# Sheet1.net
KiCad netlist of a schematic drawn in Altium Designer
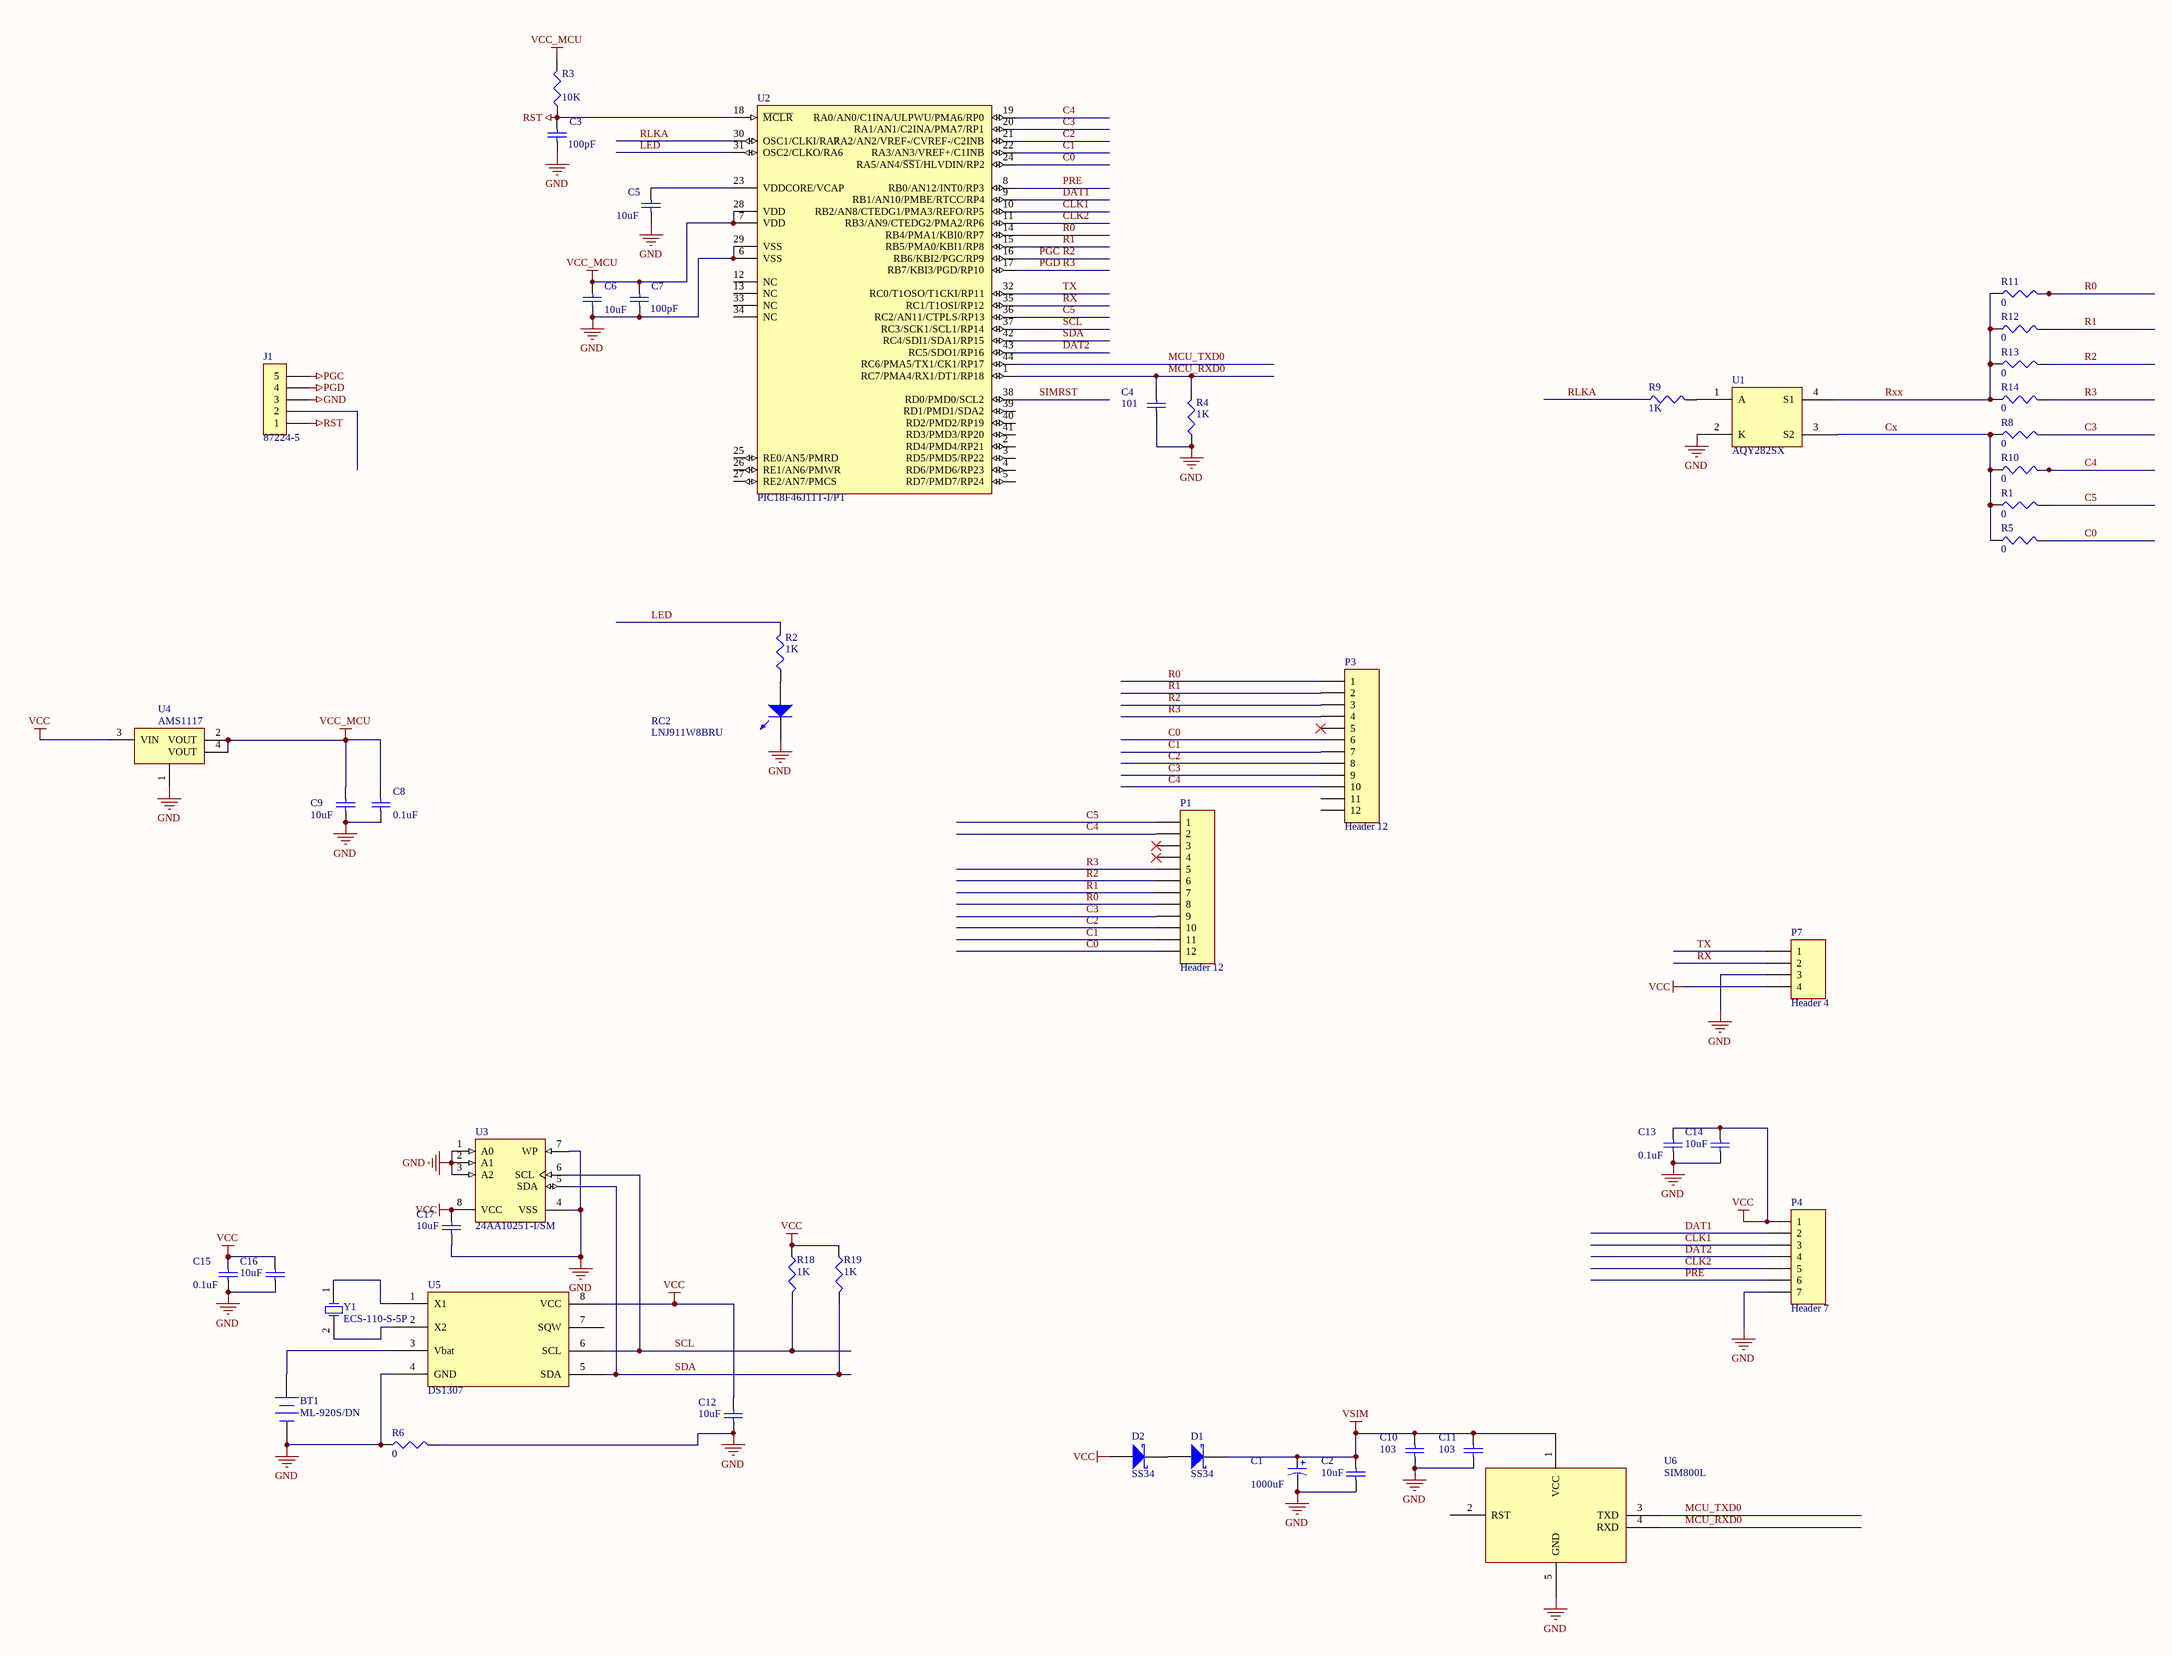
[diagram p0: Sheet1.SchDoc]

(export (version "E")
  (design (tool "Eeschema 10.0.6"))
  (components
    (comp (ref "BT1")
      (value "ML-920S/DN")
      (footprint "ML-920S/DN")
      (description "Multicell Battery")
      (fields (field (name "PUBLISHER") "Altium Limited"))
      (libsource (lib "Miscellaneous Devices") (part "Battery"))
    )
    (comp (ref "C1")
      (value "1000uF")
      (footprint "CAP8x8")
      (description "CAP ALUM 1000UF 10V 20% SMD")
      (fields (field (name "Comment") "EEE-FT1A102AP") (field (name "PUBLISHER") "Altium Limited"))
      (libsource (lib "Miscellaneous Devices") (part "Cap Pol1"))
    )
    (comp (ref "C2")
      (value "10uF")
      (footprint "RESC2012L")
      (description "CAP CER 10UF 10V Y5V 0805")
      (fields (field (name "Comment") "LMK212F106ZG-T") (field (name "PUBLISHER") "Altium Limited"))
      (libsource (lib "Miscellaneous Devices") (part "Cap"))
    )
    (comp (ref "C3")
      (value "100pF")
      (footprint "CAPC2013X05N")
      (description "Capacitor (Semiconductor SIM Model)")
      (fields (field (name "Comment") "Cap Semi") (field (name "PUBLISHER") "Altium Limited"))
      (libsource (lib "Miscellaneous Devices") (part "Cap Semi"))
    )
    (comp (ref "C4")
      (value "101")
      (footprint "RESC2012L")
      (description "CAP CER 10UF 10V Y5V 0805")
      (fields (field (name "Comment") "LMK212F106ZG-T") (field (name "PUBLISHER") "Altium Limited"))
      (libsource (lib "Miscellaneous Devices") (part "Cap"))
    )
    (comp (ref "C5")
      (value "10uF")
      (footprint "CAPC2013X05N")
      (description "Capacitor (Semiconductor SIM Model)")
      (fields (field (name "Comment") "Cap Semi") (field (name "PUBLISHER") "Altium Limited"))
      (libsource (lib "Miscellaneous Devices") (part "Cap Semi"))
    )
    (comp (ref "C6")
      (value "10uF")
      (footprint "CAPC2013X05N")
      (description "Capacitor (Semiconductor SIM Model)")
      (fields (field (name "Comment") "Cap Semi") (field (name "PUBLISHER") "Altium Limited"))
      (libsource (lib "Miscellaneous Devices") (part "Cap Semi"))
    )
    (comp (ref "C7")
      (value "100pF")
      (footprint "CAPC2013X05N")
      (description "Capacitor (Semiconductor SIM Model)")
      (fields (field (name "Comment") "Cap Semi") (field (name "PUBLISHER") "Altium Limited"))
      (libsource (lib "Miscellaneous Devices") (part "Cap Semi"))
    )
    (comp (ref "C8")
      (value "0.1uF")
      (footprint "RESC2012L")
      (description "CAP CER 0.1UF 50V Y5V 0805")
      (fields (field (name "Comment") "CL21F104ZBCNNNC") (field (name "PUBLISHER") "Altium Limited"))
      (libsource (lib "Miscellaneous Devices") (part "Cap"))
    )
    (comp (ref "C9")
      (value "10uF")
      (footprint "RESC2012L")
      (description "CAP CER 10UF 10V Y5V 0805")
      (fields (field (name "Comment") "LMK212F106ZG-T") (field (name "PUBLISHER") "Altium Limited"))
      (libsource (lib "Miscellaneous Devices") (part "Cap"))
    )
    (comp (ref "C10")
      (value "103")
      (footprint "RESC2012L")
      (description "CAP CER 10UF 10V Y5V 0805")
      (fields (field (name "Comment") "LMK212F106ZG-T") (field (name "PUBLISHER") "Altium Limited"))
      (libsource (lib "Miscellaneous Devices") (part "Cap"))
    )
    (comp (ref "C11")
      (value "103")
      (footprint "RESC2012L")
      (description "CAP CER 10UF 10V Y5V 0805")
      (fields (field (name "Comment") "LMK212F106ZG-T") (field (name "PUBLISHER") "Altium Limited"))
      (libsource (lib "Miscellaneous Devices") (part "Cap"))
    )
    (comp (ref "C12")
      (value "10uF")
      (footprint "RESC2012L")
      (description "CAP CER 10UF 10V Y5V 0805")
      (fields (field (name "Comment") "LMK212F106ZG-T") (field (name "PUBLISHER") "Altium Limited"))
      (libsource (lib "Miscellaneous Devices") (part "Cap"))
    )
    (comp (ref "C13")
      (value "0.1uF")
      (footprint "RESC2012L")
      (description "CAP CER 0.1UF 50V Y5V 0805")
      (fields (field (name "Comment") "CL21F104ZBCNNNC") (field (name "PUBLISHER") "Altium Limited"))
      (libsource (lib "Miscellaneous Devices") (part "Cap"))
    )
    (comp (ref "C14")
      (value "10uF")
      (footprint "RESC2012L")
      (description "CAP CER 10UF 10V Y5V 0805")
      (fields (field (name "Comment") "LMK212F106ZG-T") (field (name "PUBLISHER") "Altium Limited"))
      (libsource (lib "Miscellaneous Devices") (part "Cap"))
    )
    (comp (ref "C15")
      (value "0.1uF")
      (footprint "RESC2012L")
      (description "CAP CER 0.1UF 50V Y5V 0805")
      (fields (field (name "Comment") "CL21F104ZBCNNNC") (field (name "PUBLISHER") "Altium Limited"))
      (libsource (lib "Miscellaneous Devices") (part "Cap"))
    )
    (comp (ref "C16")
      (value "10uF")
      (footprint "RESC2012L")
      (description "CAP CER 10UF 10V Y5V 0805")
      (fields (field (name "Comment") "LMK212F106ZG-T") (field (name "PUBLISHER") "Altium Limited"))
      (libsource (lib "Miscellaneous Devices") (part "Cap"))
    )
    (comp (ref "C17")
      (value "10uF")
      (footprint "RESC2012L")
      (description "CAP CER 10UF 10V Y5V 0805")
      (fields (field (name "Comment") "LMK212F106ZG-T") (field (name "PUBLISHER") "Altium Limited"))
      (libsource (lib "Miscellaneous Devices") (part "Cap"))
    )
    (comp (ref "D1")
      (value "SS34")
      (footprint "SMB")
      (description "DIODE SCHOTTKY 40V 3A SMC")
      (fields (field (name "PUBLISHER") "Altium Limited"))
      (libsource (lib "Schlib1") (part "D Schottky SS34"))
    )
    (comp (ref "D2")
      (value "SS34")
      (footprint "SMB")
      (description "DIODE SCHOTTKY 40V 3A SMC")
      (fields (field (name "PUBLISHER") "Altium Limited"))
      (libsource (lib "Schlib1") (part "D Schottky SS34"))
    )
    (comp (ref "J1")
      (value "87224-5")
      (footprint "CON5")
      (description "CONN HEADER VERT .100 5POS 15AU")
      (libsource (lib "*") (part "CON5"))
    )
    (comp (ref "P1")
      (value "Header 12")
      (footprint "HDR1X12")
      (description "Header, 12-Pin")
      (fields (field (name "PUBLISHER") "Altium Limited"))
      (libsource (lib "Miscellaneous Connectors") (part "Header 12"))
    )
    (comp (ref "P3")
      (value "Header 12")
      (footprint "HDR1X12")
      (description "Header, 12-Pin")
      (fields (field (name "PUBLISHER") "Altium Limited"))
      (libsource (lib "Miscellaneous Connectors") (part "Header 12"))
    )
    (comp (ref "P4")
      (value "Header 7")
      (footprint "HDR1X7")
      (description "Header, 7-Pin")
      (fields (field (name "PUBLISHER") "Altium Limited"))
      (libsource (lib "Miscellaneous Connectors") (part "Header 7"))
    )
    (comp (ref "P7")
      (value "Header 4")
      (footprint "HDR1X4")
      (description "Header, 4-Pin")
      (fields (field (name "PUBLISHER") "Altium Limited"))
      (libsource (lib "Miscellaneous Connectors") (part "Header 4"))
    )
    (comp (ref "R1")
      (value "0")
      (footprint "JUM1")
      (description "RES 330 OHM 1/8W 5% 0805 SMD")
      (fields (field (name "Comment") "ERJ-6GEYJ331V") (field (name "PUBLISHER") "Altium Limited"))
      (libsource (lib "Miscellaneous Devices") (part "Res3"))
    )
    (comp (ref "R2")
      (value "1K")
      (footprint "RESC2012L")
      (description "RES 1K OHM 1/8W 5% 0805 SMD")
      (fields (field (name "Comment") "ERJ-6GEYJ102V") (field (name "PUBLISHER") "Altium Limited"))
      (libsource (lib "Miscellaneous Devices") (part "Res3"))
    )
    (comp (ref "R3")
      (value "10K")
      (footprint "RESC2013X05N")
      (description "Resistor")
      (fields (field (name "Comment") "Res3") (field (name "PUBLISHER") "Altium Limited"))
      (libsource (lib "Miscellaneous Devices") (part "Res3"))
    )
    (comp (ref "R4")
      (value "1K")
      (footprint "RESC2012L")
      (description "RES 1K OHM 1/8W 5% 0805 SMD")
      (fields (field (name "Comment") "ERJ-6GEYJ102V") (field (name "PUBLISHER") "Altium Limited"))
      (libsource (lib "Miscellaneous Devices") (part "Res3"))
    )
    (comp (ref "R5")
      (value "0")
      (footprint "JUM1")
      (description "RES 330 OHM 1/8W 5% 0805 SMD")
      (fields (field (name "Comment") "ERJ-6GEYJ331V") (field (name "PUBLISHER") "Altium Limited"))
      (libsource (lib "Miscellaneous Devices") (part "Res3"))
    )
    (comp (ref "R6")
      (value "0")
      (footprint "JUM1")
      (description "RES 330 OHM 1/8W 5% 0805 SMD")
      (fields (field (name "Comment") "ERJ-6GEYJ331V") (field (name "PUBLISHER") "Altium Limited"))
      (libsource (lib "Miscellaneous Devices") (part "Res3"))
    )
    (comp (ref "R8")
      (value "0")
      (footprint "JUM1")
      (description "RES 330 OHM 1/8W 5% 0805 SMD")
      (fields (field (name "Comment") "ERJ-6GEYJ331V") (field (name "PUBLISHER") "Altium Limited"))
      (libsource (lib "Miscellaneous Devices") (part "Res3"))
    )
    (comp (ref "R9")
      (value "1K")
      (footprint "RESC2012L")
      (description "RES 330 OHM 1/8W 5% 0805 SMD")
      (fields (field (name "Comment") "ERJ-6GEYJ331V") (field (name "PUBLISHER") "Altium Limited"))
      (libsource (lib "Miscellaneous Devices") (part "Res3"))
    )
    (comp (ref "R10")
      (value "0")
      (footprint "JUM1")
      (description "RES 330 OHM 1/8W 5% 0805 SMD")
      (fields (field (name "Comment") "ERJ-6GEYJ331V") (field (name "PUBLISHER") "Altium Limited"))
      (libsource (lib "Miscellaneous Devices") (part "Res3"))
    )
    (comp (ref "R11")
      (value "0")
      (footprint "JUM1")
      (description "RES 330 OHM 1/8W 5% 0805 SMD")
      (fields (field (name "Comment") "ERJ-6GEYJ331V") (field (name "PUBLISHER") "Altium Limited"))
      (libsource (lib "Miscellaneous Devices") (part "Res3"))
    )
    (comp (ref "R12")
      (value "0")
      (footprint "JUM1")
      (description "RES 330 OHM 1/8W 5% 0805 SMD")
      (fields (field (name "Comment") "ERJ-6GEYJ331V") (field (name "PUBLISHER") "Altium Limited"))
      (libsource (lib "Miscellaneous Devices") (part "Res3"))
    )
    (comp (ref "R13")
      (value "0")
      (footprint "JUM1")
      (description "RES 330 OHM 1/8W 5% 0805 SMD")
      (fields (field (name "Comment") "ERJ-6GEYJ331V") (field (name "PUBLISHER") "Altium Limited"))
      (libsource (lib "Miscellaneous Devices") (part "Res3"))
    )
    (comp (ref "R14")
      (value "0")
      (footprint "JUM1")
      (description "RES 330 OHM 1/8W 5% 0805 SMD")
      (fields (field (name "Comment") "ERJ-6GEYJ331V") (field (name "PUBLISHER") "Altium Limited"))
      (libsource (lib "Miscellaneous Devices") (part "Res3"))
    )
    (comp (ref "R18")
      (value "1K")
      (footprint "RESC2012L")
      (description "RES 330 OHM 1/8W 5% 0805 SMD")
      (fields (field (name "Comment") "ERJ-6GEYJ331V") (field (name "PUBLISHER") "Altium Limited"))
      (libsource (lib "Miscellaneous Devices") (part "Res3"))
    )
    (comp (ref "R19")
      (value "1K")
      (footprint "RESC2012L")
      (description "RES 330 OHM 1/8W 5% 0805 SMD")
      (fields (field (name "Comment") "ERJ-6GEYJ331V") (field (name "PUBLISHER") "Altium Limited"))
      (libsource (lib "Miscellaneous Devices") (part "Res3"))
    )
    (comp (ref "RC2")
      (value "LNJ911W8BRU")
      (footprint "CD3216-1206")
      (description "LED BLUE THRU BOARD 1206")
      (libsource (lib "AM335X_ZCZ") (part "LEDRED1206"))
    )
    (comp (ref "U1")
      (value "AQY282SX")
      (footprint "SOP4")
      (description "RELAY OPTO 60VAC/DC 500MA 4-SOP")
      (fields (field (name "DIGI-KEY PART NUMBER") "255-3393-2-ND"))
      (libsource (lib "Schlib1") (part "AQY282SX"))
    )
    (comp (ref "U2")
      (value "PIC18F46J11T-I/PT")
      (footprint "TQFP-PT44_N")
      (fields (field (name "PUBLISHER") "Altium Limited"))
      (libsource (lib "Microchip Microcontroller 8-Bit PIC18") (part "PIC18F46J11T-I/PT"))
    )
    (comp (ref "U3")
      (value "24AA1025T-I/SM")
      (footprint "SOIJ-SM8_N")
      (description "1 Mbit, 400kHz, 1.7V, I2C Serial EEPROM, 8-Pin SOIC 208mil, Industrial Temperature, Tape and Reel")
      (fields (field (name "PUBLISHER") "Altium Limited"))
      (libsource (lib "Microchip Memory I2C Serial EEPROM") (part "24AA1025T-I/SM"))
    )
    (comp (ref "U4")
      (value "AMS1117")
      (footprint "SOT223-4M")
      (description "Adjustable Precision Shunt Regulator")
      (fields (field (name "PUBLISHER") "Altium Limited"))
      (libsource (lib "Schlib1") (part "AMS1117"))
    )
    (comp (ref "U5") (value "DS1307") (footprint "SOIJ-SM8_N") (libsource (lib "Schlib1") (part "DS1307")))
    (comp (ref "U6") (value "SIM800L") (footprint "SIM800L") (libsource (lib "Schlib1") (part "SIM800L")))
    (comp (ref "Y1")
      (value "ECS-110-S-5P")
      (footprint "ABS07")
      (description "Crystal Oscillator")
      (fields (field (name "PUBLISHER") "Altium Limited"))
      (libsource (lib "ECS Crystal Oscillator") (part "ECS-110-S-5P"))
    )
  )
  (nets
    (net (code "1") (name "/C0") (class "Default")
      (node (ref "P1") (pin "12") (pinfunction "12_12") (pintype "passive"))
      (node (ref "P3") (pin "6") (pinfunction "6_6") (pintype "passive"))
      (node (ref "R5") (pin "1") (pinfunction "1_1") (pintype "passive"))
      (node (ref "U2") (pin "24") (pinfunction "RA5/AN4/~{SS1}/HLVDIN/RP2_24") (pintype "bidirectional"))
    )
    (net (code "2") (name "/C1") (class "Default")
      (node (ref "P1") (pin "11") (pinfunction "11_11") (pintype "passive"))
      (node (ref "P3") (pin "7") (pinfunction "7_7") (pintype "passive"))
      (node (ref "U2") (pin "22") (pinfunction "RA3/AN3/VREF+/C1INB_22") (pintype "bidirectional"))
    )
    (net (code "3") (name "/C2") (class "Default")
      (node (ref "P1") (pin "10") (pinfunction "10_10") (pintype "passive"))
      (node (ref "P3") (pin "8") (pinfunction "8_8") (pintype "passive"))
      (node (ref "U2") (pin "21") (pinfunction "RA2/AN2/VREF-/CVREF-/C2INB_21") (pintype "bidirectional"))
    )
    (net (code "4") (name "/C3") (class "Default")
      (node (ref "P1") (pin "9") (pinfunction "9_9") (pintype "passive"))
      (node (ref "P3") (pin "9") (pinfunction "9_9") (pintype "passive"))
      (node (ref "R8") (pin "1") (pinfunction "1_1") (pintype "passive"))
      (node (ref "U2") (pin "20") (pinfunction "RA1/AN1/C2INA/PMA7/RP1_20") (pintype "bidirectional"))
    )
    (net (code "5") (name "/C4") (class "Default")
      (node (ref "P1") (pin "2") (pinfunction "2_2") (pintype "passive"))
      (node (ref "P3") (pin "10") (pinfunction "10_10") (pintype "passive"))
      (node (ref "R10") (pin "1") (pinfunction "1_1") (pintype "passive"))
      (node (ref "U2") (pin "19") (pinfunction "RA0/AN0/C1INA/ULPWU/PMA6/RP0_19") (pintype "bidirectional"))
    )
    (net (code "6") (name "/C5") (class "Default")
      (node (ref "P1") (pin "1") (pinfunction "1_1") (pintype "passive"))
      (node (ref "R1") (pin "1") (pinfunction "1_1") (pintype "passive"))
      (node (ref "U2") (pin "36") (pinfunction "RC2/AN11/CTPLS/RP13_36") (pintype "bidirectional"))
    )
    (net (code "7") (name "/CLK1") (class "Default")
      (node (ref "P4") (pin "3") (pinfunction "3_3") (pintype "passive"))
      (node (ref "U2") (pin "10") (pinfunction "RB2/AN8/CTEDG1/PMA3/REFO/RP5_10") (pintype "bidirectional"))
    )
    (net (code "8") (name "/CLK2") (class "Default")
      (node (ref "P4") (pin "5") (pinfunction "5_5") (pintype "passive"))
      (node (ref "U2") (pin "11") (pinfunction "RB3/AN9/CTEDG2/PMA2/RP6_11") (pintype "bidirectional"))
    )
    (net (code "9") (name "/Cx") (class "Default")
      (node (ref "R1") (pin "2") (pinfunction "2_2") (pintype "passive"))
      (node (ref "R10") (pin "2") (pinfunction "2_2") (pintype "passive"))
      (node (ref "R5") (pin "2") (pinfunction "2_2") (pintype "passive"))
      (node (ref "R8") (pin "2") (pinfunction "2_2") (pintype "passive"))
      (node (ref "U1") (pin "3") (pinfunction "S2_3") (pintype "power_in"))
    )
    (net (code "10") (name "/DAT1") (class "Default")
      (node (ref "P4") (pin "2") (pinfunction "2_2") (pintype "passive"))
      (node (ref "U2") (pin "9") (pinfunction "RB1/AN10/PMBE/RTCC/RP4_9") (pintype "bidirectional"))
    )
    (net (code "11") (name "/DAT2") (class "Default")
      (node (ref "P4") (pin "4") (pinfunction "4_4") (pintype "passive"))
      (node (ref "U2") (pin "43") (pinfunction "RC5/SDO1/RP16_43") (pintype "bidirectional"))
    )
    (net (code "12") (name "/LED") (class "Default")
      (node (ref "R2") (pin "1") (pinfunction "1_1") (pintype "passive"))
      (node (ref "U2") (pin "31") (pinfunction "OSC2/CLKO/RA6_31") (pintype "bidirectional"))
    )
    (net (code "13") (name "/MCU_RXD0") (class "Default")
      (node (ref "C4") (pin "1") (pinfunction "1_1") (pintype "passive"))
      (node (ref "R4") (pin "1") (pinfunction "1_1") (pintype "passive"))
      (node (ref "U2") (pin "1") (pinfunction "RC7/PMA4/RX1/DT1/RP18_1") (pintype "bidirectional"))
      (node (ref "U6") (pin "4") (pinfunction "RXD_4") (pintype "power_in"))
    )
    (net (code "14") (name "/MCU_TXD0") (class "Default")
      (node (ref "U2") (pin "44") (pinfunction "RC6/PMA5/TX1/CK1/RP17_44") (pintype "bidirectional"))
      (node (ref "U6") (pin "3") (pinfunction "TXD_3") (pintype "power_in"))
    )
    (net (code "15") (name "/PRE") (class "Default")
      (node (ref "P4") (pin "6") (pinfunction "6_6") (pintype "passive"))
      (node (ref "U2") (pin "8") (pinfunction "RB0/AN12/INT0/RP3_8") (pintype "bidirectional"))
    )
    (net (code "16") (name "/R0") (class "Default")
      (node (ref "P1") (pin "8") (pinfunction "8_8") (pintype "passive"))
      (node (ref "P3") (pin "1") (pinfunction "1_1") (pintype "passive"))
      (node (ref "R11") (pin "1") (pinfunction "1_1") (pintype "passive"))
      (node (ref "U2") (pin "14") (pinfunction "RB4/PMA1/KBI0/RP7_14") (pintype "bidirectional"))
    )
    (net (code "17") (name "/R1") (class "Default")
      (node (ref "P1") (pin "7") (pinfunction "7_7") (pintype "passive"))
      (node (ref "P3") (pin "2") (pinfunction "2_2") (pintype "passive"))
      (node (ref "R12") (pin "1") (pinfunction "1_1") (pintype "passive"))
      (node (ref "U2") (pin "15") (pinfunction "RB5/PMA0/KBI1/RP8_15") (pintype "bidirectional"))
    )
    (net (code "18") (name "/RLKA") (class "Default")
      (node (ref "R9") (pin "2") (pinfunction "2_2") (pintype "passive"))
      (node (ref "U2") (pin "30") (pinfunction "OSC1/CLKI/RA7_30") (pintype "bidirectional"))
    )
    (net (code "19") (name "/RX") (class "Default")
      (node (ref "P7") (pin "2") (pinfunction "2_2") (pintype "passive"))
      (node (ref "U2") (pin "35") (pinfunction "RC1/T1OSI/RP12_35") (pintype "bidirectional"))
    )
    (net (code "20") (name "/Rxx") (class "Default")
      (node (ref "R11") (pin "2") (pinfunction "2_2") (pintype "passive"))
      (node (ref "R12") (pin "2") (pinfunction "2_2") (pintype "passive"))
      (node (ref "R13") (pin "2") (pinfunction "2_2") (pintype "passive"))
      (node (ref "R14") (pin "2") (pinfunction "2_2") (pintype "passive"))
      (node (ref "U1") (pin "4") (pinfunction "S1_4") (pintype "power_in"))
    )
    (net (code "21") (name "/SCL") (class "Default")
      (node (ref "R18") (pin "1") (pinfunction "1_1") (pintype "passive"))
      (node (ref "U2") (pin "37") (pinfunction "RC3/SCK1/SCL1/RP14_37") (pintype "bidirectional"))
      (node (ref "U3") (pin "6") (pinfunction "SCL_6") (pintype "input"))
      (node (ref "U5") (pin "6") (pinfunction "SCL_6") (pintype "passive"))
    )
    (net (code "22") (name "/SDA") (class "Default")
      (node (ref "R19") (pin "1") (pinfunction "1_1") (pintype "passive"))
      (node (ref "U2") (pin "42") (pinfunction "RC4/SDI1/SDA1/RP15_42") (pintype "bidirectional"))
      (node (ref "U3") (pin "5") (pinfunction "SDA_5") (pintype "bidirectional"))
      (node (ref "U5") (pin "5") (pinfunction "SDA_5") (pintype "passive"))
    )
    (net (code "23") (name "/SIMRST") (class "Default")
      (node (ref "U2") (pin "38") (pinfunction "RD0/PMD0/SCL2_38") (pintype "bidirectional"))
    )
    (net (code "24") (name "/TX") (class "Default")
      (node (ref "P7") (pin "1") (pinfunction "1_1") (pintype "passive"))
      (node (ref "U2") (pin "32") (pinfunction "RC0/T1OSO/T1CKI/RP11_32") (pintype "bidirectional"))
    )
    (net (code "25") (name "GND") (class "Default")
      (node (ref "BT1") (pin "2") (pinfunction "-_2") (pintype "passive"))
      (node (ref "C1") (pin "2") (pinfunction "2_2") (pintype "passive"))
      (node (ref "C10") (pin "2") (pinfunction "2_2") (pintype "passive"))
      (node (ref "C11") (pin "2") (pinfunction "2_2") (pintype "passive"))
      (node (ref "C12") (pin "2") (pinfunction "2_2") (pintype "passive"))
      (node (ref "C13") (pin "2") (pinfunction "2_2") (pintype "passive"))
      (node (ref "C14") (pin "2") (pinfunction "2_2") (pintype "passive"))
      (node (ref "C15") (pin "2") (pinfunction "2_2") (pintype "passive"))
      (node (ref "C16") (pin "2") (pinfunction "2_2") (pintype "passive"))
      (node (ref "C17") (pin "2") (pinfunction "2_2") (pintype "passive"))
      (node (ref "C2") (pin "2") (pinfunction "2_2") (pintype "passive"))
      (node (ref "C3") (pin "1") (pinfunction "1_1") (pintype "passive"))
      (node (ref "C4") (pin "2") (pinfunction "2_2") (pintype "passive"))
      (node (ref "C5") (pin "1") (pinfunction "1_1") (pintype "passive"))
      (node (ref "C6") (pin "1") (pinfunction "1_1") (pintype "passive"))
      (node (ref "C7") (pin "1") (pinfunction "1_1") (pintype "passive"))
      (node (ref "C8") (pin "2") (pinfunction "2_2") (pintype "passive"))
      (node (ref "C9") (pin "2") (pinfunction "2_2") (pintype "passive"))
      (node (ref "J1") (pin "3") (pinfunction "3_3") (pintype "passive"))
      (node (ref "P4") (pin "7") (pinfunction "7_7") (pintype "passive"))
      (node (ref "P7") (pin "3") (pinfunction "3_3") (pintype "passive"))
      (node (ref "R4") (pin "2") (pinfunction "2_2") (pintype "passive"))
      (node (ref "R6") (pin "1") (pinfunction "1_1") (pintype "passive"))
      (node (ref "R6") (pin "2") (pinfunction "2_2") (pintype "passive"))
      (node (ref "RC2") (pin "2") (pinfunction "K_2") (pintype "passive"))
      (node (ref "U1") (pin "2") (pinfunction "K_2") (pintype "power_in"))
      (node (ref "U2") (pin "29") (pinfunction "VSS_29") (pintype "power_in"))
      (node (ref "U2") (pin "6") (pinfunction "VSS_6") (pintype "power_in"))
      (node (ref "U3") (pin "1") (pinfunction "A0_1") (pintype "input"))
      (node (ref "U3") (pin "2") (pinfunction "A1_2") (pintype "input"))
      (node (ref "U3") (pin "3") (pinfunction "A2_3") (pintype "input"))
      (node (ref "U3") (pin "4") (pinfunction "VSS_4") (pintype "power_in"))
      (node (ref "U3") (pin "7") (pinfunction "WP_7") (pintype "input"))
      (node (ref "U4") (pin "1") (pinfunction "GND_1") (pintype "power_in"))
      (node (ref "U5") (pin "4") (pinfunction "GND_4") (pintype "passive"))
      (node (ref "U6") (pin "5") (pinfunction "GND_5") (pintype "power_in"))
    )
    (net (code "26") (name "Net-(BT1-+)") (class "Default")
      (node (ref "BT1") (pin "1") (pinfunction "+_1") (pintype "passive"))
      (node (ref "U5") (pin "3") (pinfunction "Vbat_3") (pintype "passive"))
    )
    (net (code "27") (name "Net-(D1-A)") (class "Default")
      (node (ref "D1") (pin "1") (pinfunction "A_1") (pintype "passive"))
      (node (ref "D2") (pin "2") (pinfunction "K_2") (pintype "passive"))
    )
    (net (code "28") (name "Net-(RC2-A)") (class "Default")
      (node (ref "R2") (pin "2") (pinfunction "2_2") (pintype "passive"))
      (node (ref "RC2") (pin "1") (pinfunction "A_1") (pintype "passive"))
    )
    (net (code "29") (name "Net-(U1-A)") (class "Default")
      (node (ref "R9") (pin "1") (pinfunction "1_1") (pintype "passive"))
      (node (ref "U1") (pin "1") (pinfunction "A_1") (pintype "power_in"))
    )
    (net (code "30") (name "Net-(U2-VDDCORE{slash}VCAP)") (class "Default")
      (node (ref "C5") (pin "2") (pinfunction "2_2") (pintype "passive"))
      (node (ref "U2") (pin "23") (pinfunction "VDDCORE/VCAP_23") (pintype "power_in"))
    )
    (net (code "31") (name "Net-(U5-X1)") (class "Default")
      (node (ref "U5") (pin "1") (pinfunction "X1_1") (pintype "passive"))
      (node (ref "Y1") (pin "1") (pinfunction "OSC1_1") (pintype "passive"))
    )
    (net (code "32") (name "Net-(U5-X2)") (class "Default")
      (node (ref "U5") (pin "2") (pinfunction "X2_2") (pintype "passive"))
      (node (ref "Y1") (pin "2") (pinfunction "OSC2_2") (pintype "passive"))
    )
    (net (code "33") (name "PGC") (class "Default")
      (node (ref "J1") (pin "5") (pinfunction "5_5") (pintype "passive"))
      (node (ref "P1") (pin "6") (pinfunction "6_6") (pintype "passive"))
      (node (ref "P3") (pin "3") (pinfunction "3_3") (pintype "passive"))
      (node (ref "R13") (pin "1") (pinfunction "1_1") (pintype "passive"))
      (node (ref "U2") (pin "16") (pinfunction "RB6/KBI2/PGC/RP9_16") (pintype "bidirectional"))
    )
    (net (code "34") (name "PGD") (class "Default")
      (node (ref "J1") (pin "4") (pinfunction "4_4") (pintype "passive"))
      (node (ref "P1") (pin "5") (pinfunction "5_5") (pintype "passive"))
      (node (ref "P3") (pin "4") (pinfunction "4_4") (pintype "passive"))
      (node (ref "R14") (pin "1") (pinfunction "1_1") (pintype "passive"))
      (node (ref "U2") (pin "17") (pinfunction "RB7/KBI3/PGD/RP10_17") (pintype "bidirectional"))
    )
    (net (code "35") (name "RST") (class "Default")
      (node (ref "C3") (pin "2") (pinfunction "2_2") (pintype "passive"))
      (node (ref "J1") (pin "1") (pinfunction "1_1") (pintype "passive"))
      (node (ref "R3") (pin "1") (pinfunction "1_1") (pintype "passive"))
      (node (ref "U2") (pin "18") (pinfunction "~{MCLR}_18") (pintype "input"))
    )
    (net (code "36") (name "VCC") (class "Default")
      (node (ref "C12") (pin "1") (pinfunction "1_1") (pintype "passive"))
      (node (ref "C13") (pin "1") (pinfunction "1_1") (pintype "passive"))
      (node (ref "C14") (pin "1") (pinfunction "1_1") (pintype "passive"))
      (node (ref "C15") (pin "1") (pinfunction "1_1") (pintype "passive"))
      (node (ref "C16") (pin "1") (pinfunction "1_1") (pintype "passive"))
      (node (ref "C17") (pin "1") (pinfunction "1_1") (pintype "passive"))
      (node (ref "D2") (pin "1") (pinfunction "A_1") (pintype "passive"))
      (node (ref "P4") (pin "1") (pinfunction "1_1") (pintype "passive"))
      (node (ref "P7") (pin "4") (pinfunction "4_4") (pintype "passive"))
      (node (ref "R18") (pin "2") (pinfunction "2_2") (pintype "passive"))
      (node (ref "R19") (pin "2") (pinfunction "2_2") (pintype "passive"))
      (node (ref "U3") (pin "8") (pinfunction "VCC_8") (pintype "power_in"))
      (node (ref "U4") (pin "3") (pinfunction "VIN_3") (pintype "power_in"))
      (node (ref "U5") (pin "8") (pinfunction "VCC_8") (pintype "passive"))
    )
    (net (code "37") (name "VCC_MCU") (class "Default")
      (node (ref "C6") (pin "2") (pinfunction "2_2") (pintype "passive"))
      (node (ref "C7") (pin "2") (pinfunction "2_2") (pintype "passive"))
      (node (ref "C8") (pin "1") (pinfunction "1_1") (pintype "passive"))
      (node (ref "C9") (pin "1") (pinfunction "1_1") (pintype "passive"))
      (node (ref "R3") (pin "2") (pinfunction "2_2") (pintype "passive"))
      (node (ref "U2") (pin "28") (pinfunction "VDD_28") (pintype "power_in"))
      (node (ref "U2") (pin "7") (pinfunction "VDD_7") (pintype "power_in"))
      (node (ref "U4") (pin "2") (pinfunction "VOUT_2") (pintype "power_in"))
      (node (ref "U4") (pin "4") (pinfunction "VOUT_4") (pintype "power_in"))
    )
    (net (code "38") (name "VSIM") (class "Default")
      (node (ref "C1") (pin "1") (pinfunction "1_1") (pintype "passive"))
      (node (ref "C10") (pin "1") (pinfunction "1_1") (pintype "passive"))
      (node (ref "C11") (pin "1") (pinfunction "1_1") (pintype "passive"))
      (node (ref "C2") (pin "1") (pinfunction "1_1") (pintype "passive"))
      (node (ref "D1") (pin "2") (pinfunction "K_2") (pintype "passive"))
      (node (ref "U6") (pin "1") (pinfunction "VCC_1") (pintype "power_in"))
    )
    (net (code "39") (name "unconnected-(J1-Pad2)") (class "Default")
      (node (ref "J1") (pin "2") (pinfunction "2_2") (pintype "passive"))
    )
    (net (code "40") (name "unconnected-(P1-Pad3)") (class "Default")
      (node (ref "P1") (pin "3") (pinfunction "3_3") (pintype "passive+no_connect"))
    )
    (net (code "41") (name "unconnected-(P1-Pad4)") (class "Default")
      (node (ref "P1") (pin "4") (pinfunction "4_4") (pintype "passive+no_connect"))
    )
    (net (code "42") (name "unconnected-(P3-Pad5)") (class "Default")
      (node (ref "P3") (pin "5") (pinfunction "5_5") (pintype "passive+no_connect"))
    )
    (net (code "43") (name "unconnected-(P3-Pad11)") (class "Default")
      (node (ref "P3") (pin "11") (pinfunction "11_11") (pintype "passive"))
    )
    (net (code "44") (name "unconnected-(P3-Pad12)") (class "Default")
      (node (ref "P3") (pin "12") (pinfunction "12_12") (pintype "passive"))
    )
    (net (code "45") (name "unconnected-(U2-NC-Pad12)") (class "Default")
      (node (ref "U2") (pin "12") (pinfunction "NC_12") (pintype "passive"))
    )
    (net (code "46") (name "unconnected-(U2-NC-Pad13)") (class "Default")
      (node (ref "U2") (pin "13") (pinfunction "NC_13") (pintype "passive"))
    )
    (net (code "47") (name "unconnected-(U2-NC-Pad33)") (class "Default")
      (node (ref "U2") (pin "33") (pinfunction "NC_33") (pintype "passive"))
    )
    (net (code "48") (name "unconnected-(U2-NC-Pad34)") (class "Default")
      (node (ref "U2") (pin "34") (pinfunction "NC_34") (pintype "passive"))
    )
    (net (code "49") (name "unconnected-(U2-RD1{slash}PMD1{slash}SDA2-Pad39)") (class "Default")
      (node (ref "U2") (pin "39") (pinfunction "RD1/PMD1/SDA2_39") (pintype "bidirectional"))
    )
    (net (code "50") (name "unconnected-(U2-RD2{slash}PMD2{slash}RP19-Pad40)") (class "Default")
      (node (ref "U2") (pin "40") (pinfunction "RD2/PMD2/RP19_40") (pintype "bidirectional"))
    )
    (net (code "51") (name "unconnected-(U2-RD3{slash}PMD3{slash}RP20-Pad41)") (class "Default")
      (node (ref "U2") (pin "41") (pinfunction "RD3/PMD3/RP20_41") (pintype "bidirectional"))
    )
    (net (code "52") (name "unconnected-(U2-RD4{slash}PMD4{slash}RP21-Pad2)") (class "Default")
      (node (ref "U2") (pin "2") (pinfunction "RD4/PMD4/RP21_2") (pintype "bidirectional"))
    )
    (net (code "53") (name "unconnected-(U2-RD5{slash}PMD5{slash}RP22-Pad3)") (class "Default")
      (node (ref "U2") (pin "3") (pinfunction "RD5/PMD5/RP22_3") (pintype "bidirectional"))
    )
    (net (code "54") (name "unconnected-(U2-RD6{slash}PMD6{slash}RP23-Pad4)") (class "Default")
      (node (ref "U2") (pin "4") (pinfunction "RD6/PMD6/RP23_4") (pintype "bidirectional"))
    )
    (net (code "55") (name "unconnected-(U2-RD7{slash}PMD7{slash}RP24-Pad5)") (class "Default")
      (node (ref "U2") (pin "5") (pinfunction "RD7/PMD7/RP24_5") (pintype "bidirectional"))
    )
    (net (code "56") (name "unconnected-(U2-RE0{slash}AN5{slash}PMRD-Pad25)") (class "Default")
      (node (ref "U2") (pin "25") (pinfunction "RE0/AN5/PMRD_25") (pintype "bidirectional"))
    )
    (net (code "57") (name "unconnected-(U2-RE1{slash}AN6{slash}PMWR-Pad26)") (class "Default")
      (node (ref "U2") (pin "26") (pinfunction "RE1/AN6/PMWR_26") (pintype "bidirectional"))
    )
    (net (code "58") (name "unconnected-(U2-RE2{slash}AN7{slash}PMCS-Pad27)") (class "Default")
      (node (ref "U2") (pin "27") (pinfunction "RE2/AN7/PMCS_27") (pintype "bidirectional"))
    )
    (net (code "59") (name "unconnected-(U5-SQW-Pad7)") (class "Default")
      (node (ref "U5") (pin "7") (pinfunction "SQW_7") (pintype "passive"))
    )
    (net (code "60") (name "unconnected-(U6-RST-Pad2)") (class "Default")
      (node (ref "U6") (pin "2") (pinfunction "RST_2") (pintype "power_in"))
    )
  )
)
